# Sheet1.net
KiCad netlist of a schematic drawn in Altium Designer
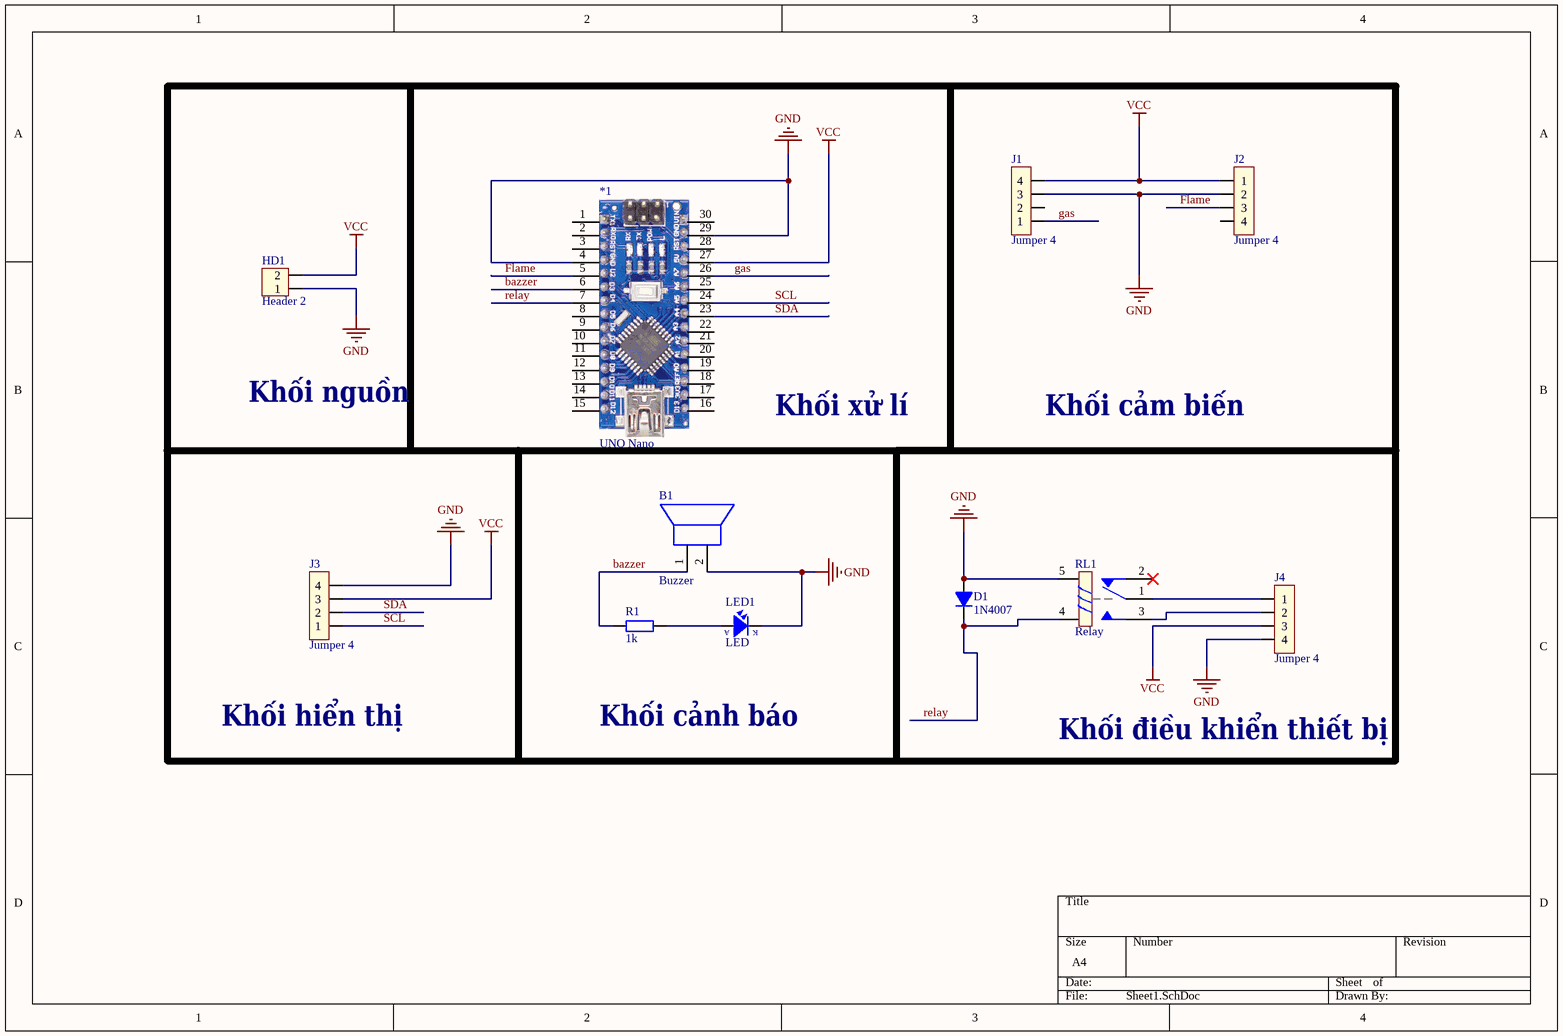
[diagram p0: Sheet1.SchDoc]

(export (version "E")
  (design (tool "Eeschema 10.0.6"))
  (components
    (comp (ref "*1") (value "UNO Nano") (footprint "UNO Nano") (libsource (lib "PART") (part "UNO Nano")))
    (comp (ref "B1")
      (value "Buzzer")
      (footprint "MinhTien_PcbLib:Buzzer")
      (libsource (lib "MinhTien_SCHLib") (part "Buzzer"))
    )
    (comp (ref "D1")
      (value "1N4007")
      (footprint "D1A")
      (description "Diode 1A")
      (libsource (lib "Thuvien3D") (part "D1A"))
    )
    (comp (ref "HD1")
      (value "Header 2")
      (footprint "PART:HED2")
      (description "Header 2 (Green)")
      (libsource (lib "PART") (part "Hed2"))
    )
    (comp (ref "J1") (value "Jumper 4") (footprint "PART:JP4") (libsource (lib "") (part "JP4_1")))
    (comp (ref "J2") (value "Jumper 4") (footprint "PART:JP4") (libsource (lib "PART") (part "JP4")))
    (comp (ref "J3") (value "Jumper 4") (footprint "PART:JP4") (libsource (lib "") (part "JP4_1")))
    (comp (ref "J4") (value "Jumper 4") (footprint "PART:JP4") (libsource (lib "PART") (part "JP4")))
    (comp (ref "LED1")
      (value "LED")
      (footprint "LED-5")
      (description "LED Single colour Green and Red")
      (libsource (lib "PART") (part "LED"))
    )
    (comp (ref "R1")
      (value "1k")
      (footprint "R1/4W")
      (description "Resistor 1/4W")
      (libsource (lib "PART") (part "R1/4W"))
    )
    (comp (ref "RL1")
      (value "Relay")
      (footprint "RL_SPDT_10A")
      (description "Relay SPDT 5 Pin")
      (libsource (lib "PART") (part "Relay 1"))
    )
  )
  (nets
    (net (code "1") (name "/Flame") (class "Default")
      (node (ref "*1") (pin "5") (pinfunction "D2_5") (pintype "passive"))
      (node (ref "J2") (pin "3") (pinfunction "3_3") (pintype "passive"))
    )
    (net (code "2") (name "/SCL") (class "Default")
      (node (ref "*1") (pin "24") (pinfunction "A5_24") (pintype "passive"))
      (node (ref "J3") (pin "1") (pinfunction "1_1") (pintype "passive"))
    )
    (net (code "3") (name "/SDA") (class "Default")
      (node (ref "*1") (pin "23") (pinfunction "A4_23") (pintype "passive"))
      (node (ref "J3") (pin "2") (pinfunction "2_2") (pintype "passive"))
    )
    (net (code "4") (name "/bazzer") (class "Default")
      (node (ref "*1") (pin "6") (pinfunction "D3_6") (pintype "passive"))
      (node (ref "B1") (pin "1") (pinfunction "+_1") (pintype "passive"))
      (node (ref "R1") (pin "1") (pinfunction "1_1") (pintype "passive"))
    )
    (net (code "5") (name "/gas") (class "Default")
      (node (ref "*1") (pin "26") (pinfunction "A7_26") (pintype "passive"))
      (node (ref "J1") (pin "1") (pinfunction "1_1") (pintype "passive"))
    )
    (net (code "6") (name "/relay") (class "Default")
      (node (ref "*1") (pin "7") (pinfunction "D4_7") (pintype "passive"))
      (node (ref "D1") (pin "2") (pinfunction "K_2") (pintype "passive"))
      (node (ref "RL1") (pin "4") (pinfunction "4_4") (pintype "passive"))
    )
    (net (code "7") (name "GND") (class "Default")
      (node (ref "*1") (pin "29") (pinfunction "GND_29") (pintype "passive"))
      (node (ref "*1") (pin "4") (pinfunction "GND_4") (pintype "passive"))
      (node (ref "B1") (pin "2") (pinfunction "-_2") (pintype "passive"))
      (node (ref "D1") (pin "1") (pinfunction "A_1") (pintype "passive"))
      (node (ref "HD1") (pin "1") (pinfunction "1_1") (pintype "passive"))
      (node (ref "J1") (pin "3") (pinfunction "3_3") (pintype "passive"))
      (node (ref "J2") (pin "2") (pinfunction "2_2") (pintype "passive"))
      (node (ref "J3") (pin "4") (pinfunction "4_4") (pintype "passive"))
      (node (ref "J4") (pin "4") (pinfunction "4_4") (pintype "passive"))
      (node (ref "LED1") (pin "2") (pinfunction "K_2") (pintype "passive"))
      (node (ref "RL1") (pin "5") (pinfunction "5_5") (pintype "passive"))
    )
    (net (code "8") (name "Net-(J4-Pad1)") (class "Default")
      (node (ref "J4") (pin "1") (pinfunction "1_1") (pintype "passive"))
      (node (ref "RL1") (pin "1") (pinfunction "1_1") (pintype "passive"))
    )
    (net (code "9") (name "Net-(J4-Pad2)") (class "Default")
      (node (ref "J4") (pin "2") (pinfunction "2_2") (pintype "passive"))
      (node (ref "RL1") (pin "3") (pinfunction "3_3") (pintype "passive"))
    )
    (net (code "10") (name "Net-(LED1-A)") (class "Default")
      (node (ref "LED1") (pin "1") (pinfunction "A_1") (pintype "passive"))
      (node (ref "R1") (pin "2") (pinfunction "2_2") (pintype "passive"))
    )
    (net (code "11") (name "VCC") (class "Default")
      (node (ref "*1") (pin "27") (pinfunction "5V_27") (pintype "passive"))
      (node (ref "HD1") (pin "2") (pinfunction "2_2") (pintype "passive"))
      (node (ref "J1") (pin "4") (pinfunction "4_4") (pintype "passive"))
      (node (ref "J2") (pin "1") (pinfunction "1_1") (pintype "passive"))
      (node (ref "J3") (pin "3") (pinfunction "3_3") (pintype "passive"))
      (node (ref "J4") (pin "3") (pinfunction "3_3") (pintype "passive"))
    )
    (net (code "12") (name "unconnected-(*1-3V3-Pad17)") (class "Default")
      (node (ref "*1") (pin "17") (pinfunction "3V3_17") (pintype "passive"))
    )
    (net (code "13") (name "unconnected-(*1-A0-Pad19)") (class "Default")
      (node (ref "*1") (pin "19") (pinfunction "A0_19") (pintype "passive"))
    )
    (net (code "14") (name "unconnected-(*1-A1-Pad20)") (class "Default")
      (node (ref "*1") (pin "20") (pinfunction "A1_20") (pintype "passive"))
    )
    (net (code "15") (name "unconnected-(*1-A2-Pad21)") (class "Default")
      (node (ref "*1") (pin "21") (pinfunction "A2_21") (pintype "passive"))
    )
    (net (code "16") (name "unconnected-(*1-A3-Pad22)") (class "Default")
      (node (ref "*1") (pin "22") (pinfunction "A3_22") (pintype "passive"))
    )
    (net (code "17") (name "unconnected-(*1-A6-Pad25)") (class "Default")
      (node (ref "*1") (pin "25") (pinfunction "A6_25") (pintype "passive"))
    )
    (net (code "18") (name "unconnected-(*1-D5-Pad8)") (class "Default")
      (node (ref "*1") (pin "8") (pinfunction "D5_8") (pintype "passive"))
    )
    (net (code "19") (name "unconnected-(*1-D6-Pad9)") (class "Default")
      (node (ref "*1") (pin "9") (pinfunction "D6_9") (pintype "passive"))
    )
    (net (code "20") (name "unconnected-(*1-D7-Pad10)") (class "Default")
      (node (ref "*1") (pin "10") (pinfunction "D7_10") (pintype "passive"))
    )
    (net (code "21") (name "unconnected-(*1-D8-Pad11)") (class "Default")
      (node (ref "*1") (pin "11") (pinfunction "D8_11") (pintype "passive"))
    )
    (net (code "22") (name "unconnected-(*1-D9-Pad12)") (class "Default")
      (node (ref "*1") (pin "12") (pinfunction "D9_12") (pintype "passive"))
    )
    (net (code "23") (name "unconnected-(*1-D10-Pad13)") (class "Default")
      (node (ref "*1") (pin "13") (pinfunction "D10_13") (pintype "passive"))
    )
    (net (code "24") (name "unconnected-(*1-D11-Pad14)") (class "Default")
      (node (ref "*1") (pin "14") (pinfunction "D11_14") (pintype "passive"))
    )
    (net (code "25") (name "unconnected-(*1-D12-Pad15)") (class "Default")
      (node (ref "*1") (pin "15") (pinfunction "D12_15") (pintype "passive"))
    )
    (net (code "26") (name "unconnected-(*1-D13-Pad16)") (class "Default")
      (node (ref "*1") (pin "16") (pinfunction "D13_16") (pintype "passive"))
    )
    (net (code "27") (name "unconnected-(*1-REF-Pad18)") (class "Default")
      (node (ref "*1") (pin "18") (pinfunction "REF_18") (pintype "passive"))
    )
    (net (code "28") (name "unconnected-(*1-RST-Pad3)") (class "Default")
      (node (ref "*1") (pin "3") (pinfunction "RST_3") (pintype "passive"))
    )
    (net (code "29") (name "unconnected-(*1-RST-Pad28)") (class "Default")
      (node (ref "*1") (pin "28") (pinfunction "RST_28") (pintype "passive"))
    )
    (net (code "30") (name "unconnected-(*1-RX-Pad2)") (class "Default")
      (node (ref "*1") (pin "2") (pinfunction "RX_2") (pintype "passive"))
    )
    (net (code "31") (name "unconnected-(*1-TX-Pad1)") (class "Default")
      (node (ref "*1") (pin "1") (pinfunction "TX_1") (pintype "passive"))
    )
    (net (code "32") (name "unconnected-(*1-VIN-Pad30)") (class "Default")
      (node (ref "*1") (pin "30") (pinfunction "VIN_30") (pintype "passive"))
    )
    (net (code "33") (name "unconnected-(J1-Pad2)") (class "Default")
      (node (ref "J1") (pin "2") (pinfunction "2_2") (pintype "passive"))
    )
    (net (code "34") (name "unconnected-(J2-Pad4)") (class "Default")
      (node (ref "J2") (pin "4") (pinfunction "4_4") (pintype "passive"))
    )
    (net (code "35") (name "unconnected-(RL1-Pad2)") (class "Default")
      (node (ref "RL1") (pin "2") (pinfunction "2_2") (pintype "passive+no_connect"))
    )
  )
)
